# BQ24171_DC.net
KiCad netlist of a schematic drawn in EAGLE
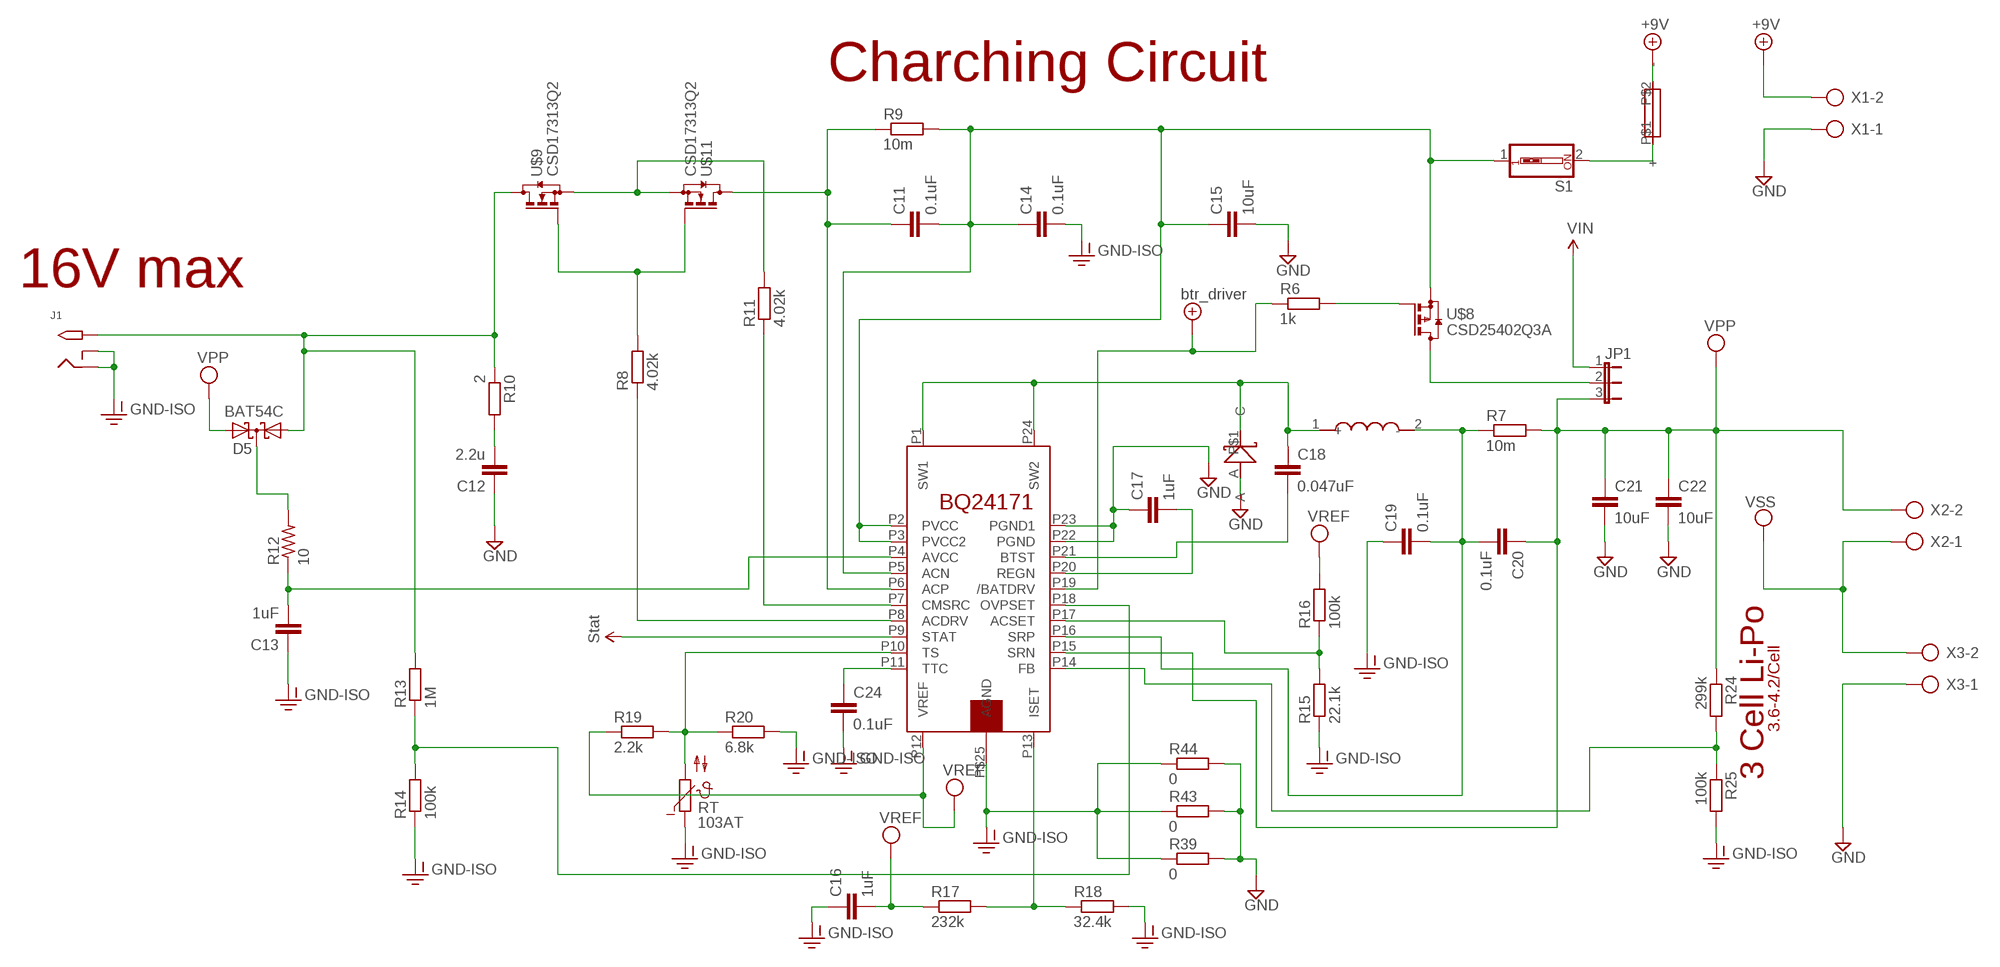
[diagram p0: schematic, sheet 1]

(export (version "E")
  (design (tool "Eeschema 10.0.6"))
  (components
    (comp (ref "B220-1")
      (value "B220")
      (footprint "eagle-import:SMA")
      (libsource (lib "eagle-import") (part "B220"))
    )
    (comp (ref "C11")
      (value "0.1uF")
      (footprint "eagle-import:C1206")
      (libsource (lib "eagle-import") (part "C-EUC1206"))
    )
    (comp (ref "C12")
      (value "2.2u")
      (footprint "eagle-import:C1206")
      (libsource (lib "eagle-import") (part "C-EUC1206"))
    )
    (comp (ref "C13")
      (value "1uF")
      (footprint "eagle-import:C1206")
      (libsource (lib "eagle-import") (part "C-EUC1206"))
    )
    (comp (ref "C14")
      (value "0.1uF")
      (footprint "eagle-import:C1206")
      (libsource (lib "eagle-import") (part "C-EUC1206"))
    )
    (comp (ref "C15")
      (value "10uF")
      (footprint "eagle-import:C1206")
      (libsource (lib "eagle-import") (part "C-EUC1206"))
    )
    (comp (ref "C16")
      (value "1uF")
      (footprint "eagle-import:C1206")
      (libsource (lib "eagle-import") (part "C-EUC1206"))
    )
    (comp (ref "C17")
      (value "1uF")
      (footprint "eagle-import:C1206")
      (libsource (lib "eagle-import") (part "C-EUC1206"))
    )
    (comp (ref "C18")
      (value "0.047uF")
      (footprint "eagle-import:C1206")
      (libsource (lib "eagle-import") (part "C-EUC1206"))
    )
    (comp (ref "C19")
      (value "0.1uF")
      (footprint "eagle-import:C1206")
      (libsource (lib "eagle-import") (part "C-EUC1206"))
    )
    (comp (ref "C20")
      (value "0.1uF")
      (footprint "eagle-import:C1206")
      (libsource (lib "eagle-import") (part "C-EUC1206"))
    )
    (comp (ref "C21")
      (value "10uF")
      (footprint "eagle-import:C1206")
      (libsource (lib "eagle-import") (part "C-EUC1206"))
    )
    (comp (ref "C22")
      (value "10uF")
      (footprint "eagle-import:C1206")
      (libsource (lib "eagle-import") (part "C-EUC1206"))
    )
    (comp (ref "C24")
      (value "0.1uF")
      (footprint "eagle-import:C1206")
      (libsource (lib "eagle-import") (part "C-EUC1206"))
    )
    (comp (ref "D5")
      (value "BAT54C")
      (footprint "eagle-import:SOT23")
      (libsource (lib "eagle-import") (part "BAT54C"))
    )
    (comp (ref "J1")
      (value "2.1MMJACKTHM")
      (footprint "eagle-import:PJ-102A")
      (libsource (lib "eagle-import") (part "2.1MMJACKTHM"))
    )
    (comp (ref "JP1")
      (value "JP2E")
      (footprint "eagle-import:JP2")
      (libsource (lib "eagle-import") (part "JP2E"))
    )
    (comp (ref "R6")
      (value "1k")
      (footprint "eagle-import:M1206")
      (libsource (lib "eagle-import") (part "R-EU_M1206"))
    )
    (comp (ref "R7")
      (value "10m")
      (footprint "eagle-import:R1206")
      (libsource (lib "eagle-import") (part "R-EU_R1206"))
    )
    (comp (ref "R8")
      (value "4.02k")
      (footprint "eagle-import:R1206")
      (libsource (lib "eagle-import") (part "R-EU_R1206"))
    )
    (comp (ref "R9")
      (value "10m")
      (footprint "eagle-import:R1206")
      (libsource (lib "eagle-import") (part "R-EU_R1206"))
    )
    (comp (ref "R10")
      (value "2")
      (footprint "eagle-import:R1206")
      (libsource (lib "eagle-import") (part "R-EU_R1206"))
    )
    (comp (ref "R11")
      (value "4.02k")
      (footprint "eagle-import:R1206")
      (libsource (lib "eagle-import") (part "R-EU_R1206"))
    )
    (comp (ref "R12")
      (value "10")
      (footprint "eagle-import:R1206")
      (libsource (lib "eagle-import") (part "R-US_R1206"))
    )
    (comp (ref "R13")
      (value "1M")
      (footprint "eagle-import:R1206")
      (libsource (lib "eagle-import") (part "R-EU_R1206"))
    )
    (comp (ref "R14")
      (value "100k")
      (footprint "eagle-import:R1206")
      (libsource (lib "eagle-import") (part "R-EU_R1206"))
    )
    (comp (ref "R15")
      (value "22.1k")
      (footprint "eagle-import:R1206")
      (libsource (lib "eagle-import") (part "R-EU_R1206"))
    )
    (comp (ref "R16")
      (value "100k")
      (footprint "eagle-import:M1206")
      (libsource (lib "eagle-import") (part "R-EU_M1206"))
    )
    (comp (ref "R17")
      (value "232k")
      (footprint "eagle-import:R1206")
      (libsource (lib "eagle-import") (part "R-EU_R1206"))
    )
    (comp (ref "R18")
      (value "32.4k")
      (footprint "eagle-import:M1206")
      (libsource (lib "eagle-import") (part "R-EU_M1206"))
    )
    (comp (ref "R19")
      (value "2.2k")
      (footprint "eagle-import:R1206")
      (libsource (lib "eagle-import") (part "R-EU_R1206"))
    )
    (comp (ref "R20")
      (value "6.8k")
      (footprint "eagle-import:R1206")
      (libsource (lib "eagle-import") (part "R-EU_R1206"))
    )
    (comp (ref "R24")
      (value "299k")
      (footprint "eagle-import:R1206")
      (libsource (lib "eagle-import") (part "R-EU_R1206"))
    )
    (comp (ref "R25")
      (value "100k")
      (footprint "eagle-import:R1206")
      (libsource (lib "eagle-import") (part "R-EU_R1206"))
    )
    (comp (ref "R39")
      (value "0")
      (footprint "eagle-import:R1206")
      (libsource (lib "eagle-import") (part "R-EU_R1206"))
    )
    (comp (ref "R43")
      (value "0")
      (footprint "eagle-import:R1206")
      (libsource (lib "eagle-import") (part "R-EU_R1206"))
    )
    (comp (ref "R44")
      (value "0")
      (footprint "eagle-import:R1206")
      (libsource (lib "eagle-import") (part "R-EU_R1206"))
    )
    (comp (ref "RT")
      (value "103AT")
      (footprint "eagle-import:P640")
      (libsource (lib "eagle-import") (part "NTC640"))
    )
    (comp (ref "S1")
      (value "SW_DIP-1")
      (footprint "eagle-import:EDG-01")
      (libsource (lib "eagle-import") (part "SW_DIP-1"))
    )
    (comp (ref "U$5")
      (value "BQ24171")
      (footprint "eagle-import:VQFN-N24")
      (libsource (lib "eagle-import") (part "BQ24171"))
    )
    (comp (ref "U$7")
      (value "3.3uH")
      (footprint "eagle-import:IHLP-202CZ-01")
      (libsource (lib "eagle-import") (part "IHLP-2020CZ-01"))
    )
    (comp (ref "U$8")
      (value "CSD25402Q3A")
      (footprint "eagle-import:Q3A")
      (libsource (lib "eagle-import") (part "CSD25402Q3A"))
    )
    (comp (ref "U$9")
      (value "CSD17313Q2")
      (footprint "eagle-import:Q2")
      (libsource (lib "eagle-import") (part "CSD17313Q2"))
    )
    (comp (ref "U$11")
      (value "CSD17313Q2")
      (footprint "eagle-import:Q2")
      (libsource (lib "eagle-import") (part "CSD17313Q2"))
    )
    (comp (ref "U$17")
      (value "FUSE")
      (footprint "eagle-import:1808")
      (libsource (lib "eagle-import") (part "FUSE"))
    )
    (comp (ref "X1")
      (value "AK300/2")
      (footprint "eagle-import:AK300_2")
      (libsource (lib "eagle-import") (part "AK300/2"))
    )
    (comp (ref "X2")
      (value "AK300/2")
      (footprint "eagle-import:AK300_2")
      (libsource (lib "eagle-import") (part "AK300/2"))
    )
    (comp (ref "X3")
      (value "AK300/2")
      (footprint "eagle-import:AK300_2")
      (libsource (lib "eagle-import") (part "AK300/2"))
    )
  )
  (nets
    (net (code "1") (name "+9V") (class "Default")
      (node (ref "U$17") (pin "P$2") (pinfunction "-_P$2") (pintype "bidirectional"))
      (node (ref "X1") (pin "2") (pinfunction "KL_2") (pintype "passive"))
    )
    (net (code "2") (name "GND") (class "Default")
      (node (ref "B220-1") (pin "A") (pinfunction "A_A") (pintype "bidirectional"))
      (node (ref "C12") (pin "1") (pinfunction "1_1") (pintype "passive"))
      (node (ref "C15") (pin "2") (pinfunction "2_2") (pintype "passive"))
      (node (ref "C17") (pin "1") (pinfunction "1_1") (pintype "passive"))
      (node (ref "C21") (pin "2") (pinfunction "2_2") (pintype "passive"))
      (node (ref "C22") (pin "2") (pinfunction "2_2") (pintype "passive"))
      (node (ref "R39") (pin "2") (pinfunction "2_2") (pintype "passive"))
      (node (ref "R43") (pin "2") (pinfunction "2_2") (pintype "passive"))
      (node (ref "R44") (pin "2") (pinfunction "2_2") (pintype "passive"))
      (node (ref "U$5") (pin "P22") (pinfunction "PGND_P22") (pintype "bidirectional"))
      (node (ref "U$5") (pin "P23") (pinfunction "PGND1_P23") (pintype "bidirectional"))
      (node (ref "X1") (pin "1") (pinfunction "KL_1") (pintype "passive"))
      (node (ref "X3") (pin "1") (pinfunction "KL_1") (pintype "passive"))
    )
    (net (code "3") (name "GND-ISO") (class "Default")
      (node (ref "C13") (pin "1") (pinfunction "1_1") (pintype "passive"))
      (node (ref "C14") (pin "2") (pinfunction "2_2") (pintype "passive"))
      (node (ref "C16") (pin "1") (pinfunction "1_1") (pintype "passive"))
      (node (ref "C19") (pin "1") (pinfunction "1_1") (pintype "passive"))
      (node (ref "C24") (pin "2") (pinfunction "2_2") (pintype "passive"))
      (node (ref "J1") (pin "RING") (pinfunction "RING_RING") (pintype "bidirectional"))
      (node (ref "J1") (pin "RING_SW") (pinfunction "RING_SW_RING_SW") (pintype "bidirectional"))
      (node (ref "R14") (pin "1") (pinfunction "1_1") (pintype "passive"))
      (node (ref "R15") (pin "1") (pinfunction "1_1") (pintype "passive"))
      (node (ref "R18") (pin "2") (pinfunction "2_2") (pintype "passive"))
      (node (ref "R20") (pin "2") (pinfunction "2_2") (pintype "passive"))
      (node (ref "R25") (pin "2") (pinfunction "2_2") (pintype "passive"))
      (node (ref "R39") (pin "1") (pinfunction "1_1") (pintype "passive"))
      (node (ref "R43") (pin "1") (pinfunction "1_1") (pintype "passive"))
      (node (ref "R44") (pin "1") (pinfunction "1_1") (pintype "passive"))
      (node (ref "RT") (pin "1") (pinfunction "1_1") (pintype "passive"))
      (node (ref "U$5") (pin "P$25") (pinfunction "AGND_P$25") (pintype "bidirectional"))
    )
    (net (code "4") (name "Net-(B220-1-C)") (class "Default")
      (node (ref "B220-1") (pin "P$1") (pinfunction "C_P$1") (pintype "bidirectional"))
      (node (ref "C18") (pin "1") (pinfunction "1_1") (pintype "passive"))
      (node (ref "U$5") (pin "P1") (pinfunction "SW1_P1") (pintype "bidirectional"))
      (node (ref "U$5") (pin "P24") (pinfunction "SW2_P24") (pintype "bidirectional"))
      (node (ref "U$7") (pin "1") (pinfunction "+_1") (pintype "bidirectional"))
    )
    (net (code "5") (name "Net-(C12-Pad2)") (class "Default")
      (node (ref "C12") (pin "2") (pinfunction "2_2") (pintype "passive"))
      (node (ref "R10") (pin "2") (pinfunction "2_2") (pintype "passive"))
    )
    (net (code "6") (name "Net-(D5-A1)") (class "Default")
      (node (ref "D5") (pin "1") (pinfunction "A1_1") (pintype "passive"))
      (node (ref "J1") (pin "TIP") (pinfunction "TIP_TIP") (pintype "bidirectional"))
      (node (ref "R10") (pin "1") (pinfunction "1_1") (pintype "passive"))
      (node (ref "R13") (pin "2") (pinfunction "2_2") (pintype "passive"))
      (node (ref "U$9") (pin "1") (pinfunction "D_1") (pintype "passive"))
      (node (ref "U$9") (pin "2") (pinfunction "D_2") (pintype "passive"))
      (node (ref "U$9") (pin "5") (pinfunction "D_5") (pintype "passive"))
      (node (ref "U$9") (pin "6") (pinfunction "D_6") (pintype "passive"))
      (node (ref "U$9") (pin "8") (pinfunction "D_8") (pintype "passive"))
    )
    (net (code "7") (name "Net-(D5-CC)") (class "Default")
      (node (ref "D5") (pin "3") (pinfunction "CC_3") (pintype "passive"))
      (node (ref "R12") (pin "2") (pinfunction "2_2") (pintype "passive"))
    )
    (net (code "8") (name "Net-(JP1-Pad2)") (class "Default")
      (node (ref "JP1") (pin "2") (pinfunction "2_2") (pintype "passive"))
      (node (ref "U$8") (pin "1") (pinfunction "D_1") (pintype "passive"))
      (node (ref "U$8") (pin "2") (pinfunction "D_2") (pintype "passive"))
      (node (ref "U$8") (pin "3") (pinfunction "D_3") (pintype "passive"))
    )
    (net (code "9") (name "Net-(R11-Pad2)") (class "Default")
      (node (ref "R11") (pin "2") (pinfunction "2_2") (pintype "passive"))
      (node (ref "U$11") (pin "4") (pinfunction "S_4") (pintype "passive"))
      (node (ref "U$11") (pin "7") (pinfunction "S_7") (pintype "passive"))
      (node (ref "U$9") (pin "4") (pinfunction "S_4") (pintype "passive"))
      (node (ref "U$9") (pin "7") (pinfunction "S_7") (pintype "passive"))
    )
    (net (code "10") (name "Net-(U$5-ACDRV)") (class "Default")
      (node (ref "R8") (pin "1") (pinfunction "1_1") (pintype "passive"))
      (node (ref "U$5") (pin "P8") (pinfunction "ACDRV_P8") (pintype "bidirectional"))
    )
    (net (code "11") (name "Net-(U$5-ACN)") (class "Default")
      (node (ref "C11") (pin "2") (pinfunction "2_2") (pintype "passive"))
      (node (ref "C14") (pin "1") (pinfunction "1_1") (pintype "passive"))
      (node (ref "C15") (pin "1") (pinfunction "1_1") (pintype "passive"))
      (node (ref "R9") (pin "2") (pinfunction "2_2") (pintype "passive"))
      (node (ref "S1") (pin "1") (pinfunction "1_1") (pintype "passive"))
      (node (ref "U$5") (pin "P2") (pinfunction "PVCC_P2") (pintype "bidirectional"))
      (node (ref "U$5") (pin "P3") (pinfunction "PVCC2_P3") (pintype "bidirectional"))
      (node (ref "U$5") (pin "P5") (pinfunction "ACN_P5") (pintype "bidirectional"))
      (node (ref "U$8") (pin "5") (pinfunction "S_5") (pintype "passive"))
      (node (ref "U$8") (pin "6") (pinfunction "S_6") (pintype "passive"))
      (node (ref "U$8") (pin "7") (pinfunction "S_7") (pintype "passive"))
      (node (ref "U$8") (pin "8") (pinfunction "S_8") (pintype "passive"))
      (node (ref "U$8") (pin "P$5") (pinfunction "S_P$5") (pintype "passive"))
    )
    (net (code "12") (name "Net-(U$5-ACP)") (class "Default")
      (node (ref "C11") (pin "1") (pinfunction "1_1") (pintype "passive"))
      (node (ref "R9") (pin "1") (pinfunction "1_1") (pintype "passive"))
      (node (ref "U$11") (pin "1") (pinfunction "D_1") (pintype "passive"))
      (node (ref "U$11") (pin "2") (pinfunction "D_2") (pintype "passive"))
      (node (ref "U$11") (pin "5") (pinfunction "D_5") (pintype "passive"))
      (node (ref "U$11") (pin "6") (pinfunction "D_6") (pintype "passive"))
      (node (ref "U$11") (pin "8") (pinfunction "D_8") (pintype "passive"))
      (node (ref "U$5") (pin "P6") (pinfunction "ACP_P6") (pintype "bidirectional"))
    )
    (net (code "13") (name "Net-(U$5-ACSET)") (class "Default")
      (node (ref "R15") (pin "2") (pinfunction "2_2") (pintype "passive"))
      (node (ref "R16") (pin "1") (pinfunction "1_1") (pintype "passive"))
      (node (ref "U$5") (pin "P17") (pinfunction "ACSET_P17") (pintype "bidirectional"))
    )
    (net (code "14") (name "Net-(U$5-AVCC)") (class "Default")
      (node (ref "C13") (pin "2") (pinfunction "2_2") (pintype "passive"))
      (node (ref "R12") (pin "1") (pinfunction "1_1") (pintype "passive"))
      (node (ref "U$5") (pin "P4") (pinfunction "AVCC_P4") (pintype "bidirectional"))
    )
    (net (code "15") (name "Net-(U$5-BTST)") (class "Default")
      (node (ref "C18") (pin "2") (pinfunction "2_2") (pintype "passive"))
      (node (ref "U$5") (pin "P21") (pinfunction "BTST_P21") (pintype "bidirectional"))
    )
    (net (code "16") (name "Net-(U$5-CMSRC)") (class "Default")
      (node (ref "R11") (pin "1") (pinfunction "1_1") (pintype "passive"))
      (node (ref "U$5") (pin "P7") (pinfunction "CMSRC_P7") (pintype "bidirectional"))
    )
    (net (code "17") (name "Net-(U$5-FB)") (class "Default")
      (node (ref "R24") (pin "2") (pinfunction "2_2") (pintype "passive"))
      (node (ref "R25") (pin "1") (pinfunction "1_1") (pintype "passive"))
      (node (ref "U$5") (pin "P14") (pinfunction "FB_P14") (pintype "bidirectional"))
    )
    (net (code "18") (name "Net-(U$5-ISET)") (class "Default")
      (node (ref "R17") (pin "2") (pinfunction "2_2") (pintype "passive"))
      (node (ref "R18") (pin "1") (pinfunction "1_1") (pintype "passive"))
      (node (ref "U$5") (pin "P13") (pinfunction "ISET_P13") (pintype "bidirectional"))
    )
    (net (code "19") (name "Net-(U$5-OVPSET)") (class "Default")
      (node (ref "R13") (pin "1") (pinfunction "1_1") (pintype "passive"))
      (node (ref "R14") (pin "2") (pinfunction "2_2") (pintype "passive"))
      (node (ref "U$5") (pin "P18") (pinfunction "OVPSET_P18") (pintype "bidirectional"))
    )
    (net (code "20") (name "Net-(U$5-REGN)") (class "Default")
      (node (ref "C17") (pin "2") (pinfunction "2_2") (pintype "passive"))
      (node (ref "U$5") (pin "P20") (pinfunction "REGN_P20") (pintype "bidirectional"))
    )
    (net (code "21") (name "Net-(U$5-SRP)") (class "Default")
      (node (ref "C19") (pin "2") (pinfunction "2_2") (pintype "passive"))
      (node (ref "C20") (pin "2") (pinfunction "2_2") (pintype "passive"))
      (node (ref "R7") (pin "1") (pinfunction "1_1") (pintype "passive"))
      (node (ref "U$5") (pin "P16") (pinfunction "SRP_P16") (pintype "bidirectional"))
      (node (ref "U$7") (pin "2") (pinfunction "-_2") (pintype "bidirectional"))
    )
    (net (code "22") (name "Net-(U$5-TS)") (class "Default")
      (node (ref "R19") (pin "2") (pinfunction "2_2") (pintype "passive"))
      (node (ref "R20") (pin "1") (pinfunction "1_1") (pintype "passive"))
      (node (ref "RT") (pin "2") (pinfunction "2_2") (pintype "passive"))
      (node (ref "U$5") (pin "P10") (pinfunction "TS_P10") (pintype "bidirectional"))
    )
    (net (code "23") (name "Net-(U$5-TTC)") (class "Default")
      (node (ref "C24") (pin "1") (pinfunction "1_1") (pintype "passive"))
      (node (ref "U$5") (pin "P11") (pinfunction "TTC_P11") (pintype "bidirectional"))
    )
    (net (code "24") (name "Net-(U$8-G)") (class "Default")
      (node (ref "R6") (pin "2") (pinfunction "2_2") (pintype "passive"))
      (node (ref "U$8") (pin "4") (pinfunction "G_4") (pintype "passive"))
    )
    (net (code "25") (name "Net-(U$11-G)") (class "Default")
      (node (ref "R8") (pin "2") (pinfunction "2_2") (pintype "passive"))
      (node (ref "U$11") (pin "3") (pinfunction "G_3") (pintype "passive"))
      (node (ref "U$9") (pin "3") (pinfunction "G_3") (pintype "passive"))
    )
    (net (code "26") (name "Net-(U$17-+)") (class "Default")
      (node (ref "S1") (pin "2") (pinfunction "2_2") (pintype "passive"))
      (node (ref "U$17") (pin "P$1") (pinfunction "+_P$1") (pintype "bidirectional"))
    )
    (net (code "27") (name "Stat") (class "Default")
      (node (ref "U$5") (pin "P9") (pinfunction "STAT_P9") (pintype "bidirectional"))
    )
    (net (code "28") (name "VIN") (class "Default")
      (node (ref "JP1") (pin "1") (pinfunction "1_1") (pintype "passive"))
    )
    (net (code "29") (name "VPP") (class "Default")
      (node (ref "C20") (pin "1") (pinfunction "1_1") (pintype "passive"))
      (node (ref "C21") (pin "1") (pinfunction "1_1") (pintype "passive"))
      (node (ref "C22") (pin "1") (pinfunction "1_1") (pintype "passive"))
      (node (ref "D5") (pin "2") (pinfunction "A2_2") (pintype "passive"))
      (node (ref "JP1") (pin "3") (pinfunction "3_3") (pintype "passive"))
      (node (ref "R24") (pin "1") (pinfunction "1_1") (pintype "passive"))
      (node (ref "R7") (pin "2") (pinfunction "2_2") (pintype "passive"))
      (node (ref "U$5") (pin "P15") (pinfunction "SRN_P15") (pintype "bidirectional"))
      (node (ref "X2") (pin "2") (pinfunction "KL_2") (pintype "passive"))
    )
    (net (code "30") (name "VREF") (class "Default")
      (node (ref "C16") (pin "2") (pinfunction "2_2") (pintype "passive"))
      (node (ref "R16") (pin "2") (pinfunction "2_2") (pintype "passive"))
      (node (ref "R17") (pin "1") (pinfunction "1_1") (pintype "passive"))
      (node (ref "R19") (pin "1") (pinfunction "1_1") (pintype "passive"))
      (node (ref "U$5") (pin "P12") (pinfunction "VREF_P12") (pintype "bidirectional"))
    )
    (net (code "31") (name "VSS") (class "Default")
      (node (ref "X2") (pin "1") (pinfunction "KL_1") (pintype "passive"))
      (node (ref "X3") (pin "2") (pinfunction "KL_2") (pintype "passive"))
    )
    (net (code "32") (name "btr_driver") (class "Default")
      (node (ref "R6") (pin "1") (pinfunction "1_1") (pintype "passive"))
      (node (ref "U$5") (pin "P19") (pinfunction "/BATDRV_P19") (pintype "bidirectional"))
    )
  )
)
